# schematic.net
KiCad netlist of a schematic drawn in Altium Designer
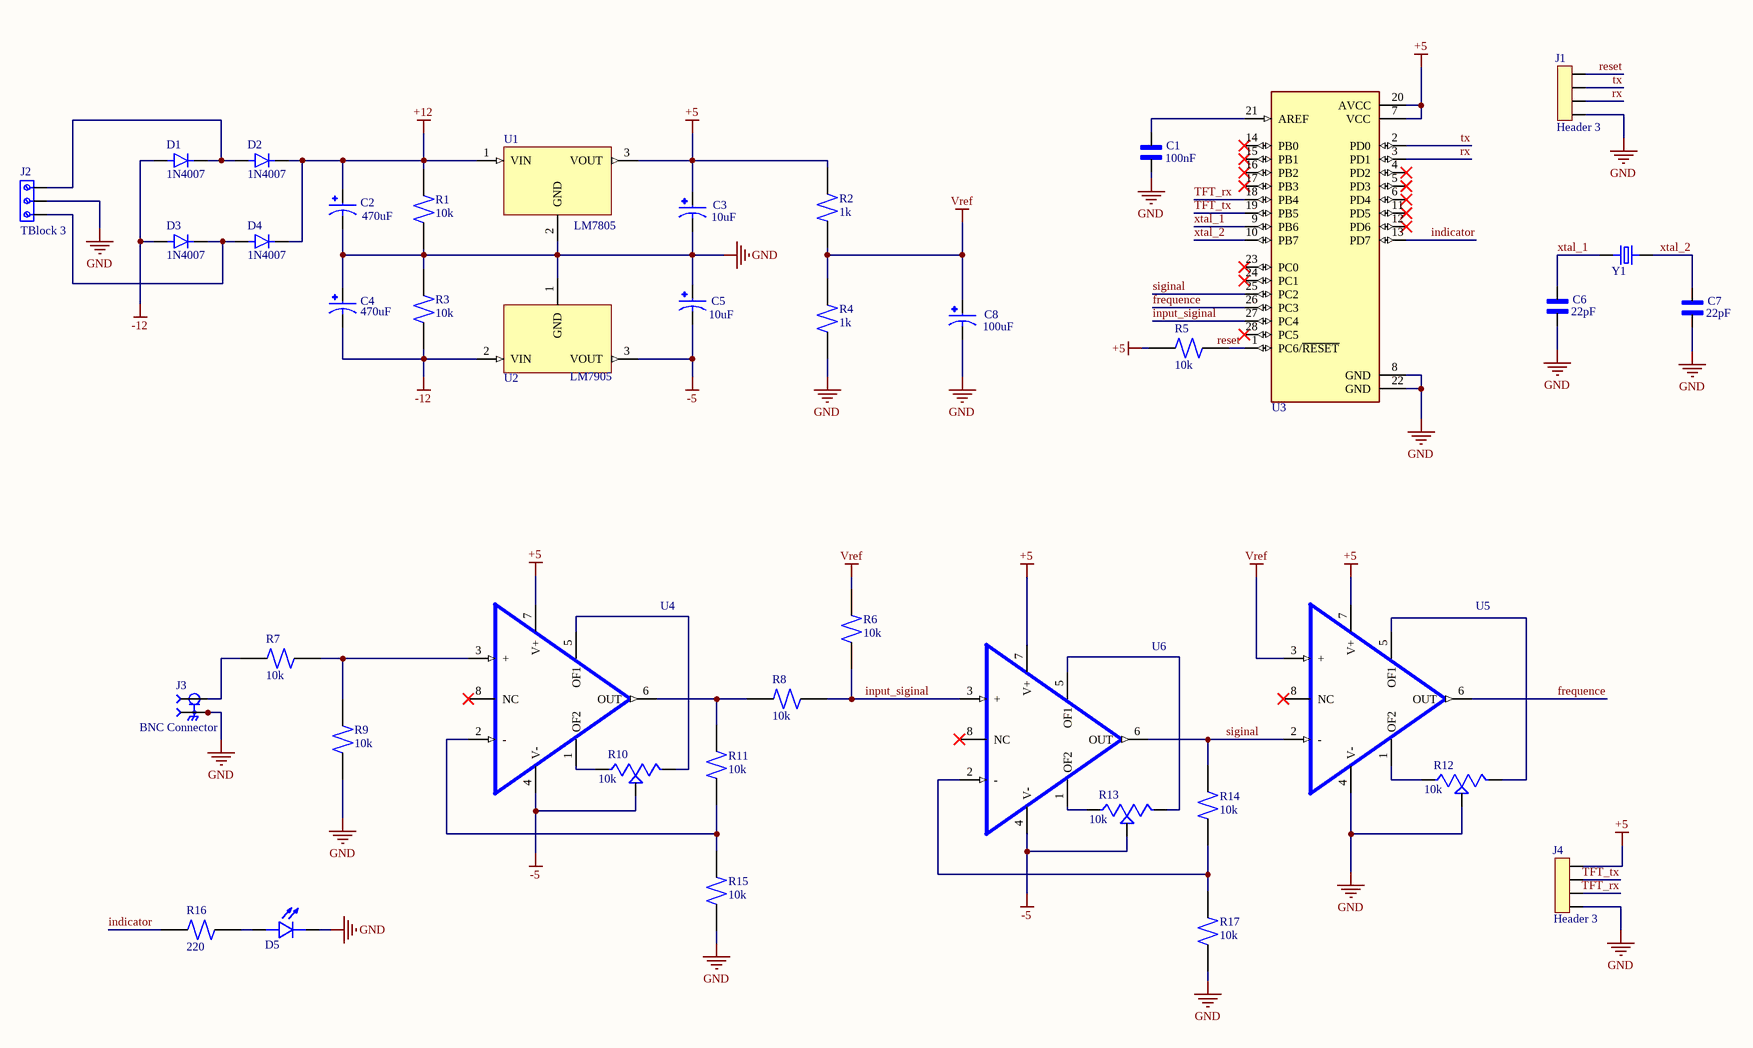
[diagram p0: schematic.SchDoc]

(export (version "E")
  (design (tool "Eeschema 10.0.6"))
  (components
    (comp (ref "C1")
      (value "100nF")
      (footprint "CAPRB500W50L450T300H550")
      (description "2200 pF Â±10% 250V Ceramic Capacitor X7R Radial")
      (fields (field (name "DIGI-KEY_PART_NUMBER") "445-173386-1-ND") (field (name "MF") "TDK"))
      (libsource (lib "Installed library") (part "Ceramic capacitor"))
    )
    (comp (ref "C2")
      (value "470uF")
      (footprint "CAPPRD500W50D500H1100")
      (description "FS-A")
      (fields (field (name "MF") "{'manufacturer': u'Panasonic'}") (field (name "MP") "EEUFS0J221B"))
      (libsource (lib "Installed library") (part "Electrolytic capacitor"))
    )
    (comp (ref "C3")
      (value "10uF")
      (footprint "CAPPRD500W50D500H1100")
      (description "FS-A")
      (fields (field (name "MF") "{'manufacturer': u'Panasonic'}") (field (name "MP") "EEUFS0J221B"))
      (libsource (lib "Installed library") (part "Electrolytic capacitor"))
    )
    (comp (ref "C4")
      (value "470uF")
      (footprint "CAPPRD500W50D500H1100")
      (description "FS-A")
      (fields (field (name "MF") "{'manufacturer': u'Panasonic'}") (field (name "MP") "EEUFS0J221B"))
      (libsource (lib "Installed library") (part "Electrolytic capacitor"))
    )
    (comp (ref "C5")
      (value "10uF")
      (footprint "CAPPRD500W50D500H1100")
      (description "FS-A")
      (fields (field (name "MF") "{'manufacturer': u'Panasonic'}") (field (name "MP") "EEUFS0J221B"))
      (libsource (lib "Installed library") (part "Electrolytic capacitor"))
    )
    (comp (ref "C6")
      (value "22pF")
      (footprint "CAPRB500W50L450T300H550")
      (description "2200 pF Â±10% 250V Ceramic Capacitor X7R Radial")
      (fields (field (name "DIGI-KEY_PART_NUMBER") "445-173386-1-ND") (field (name "MF") "TDK"))
      (libsource (lib "Installed library") (part "Ceramic capacitor"))
    )
    (comp (ref "C7")
      (value "22pF")
      (footprint "CAPRB500W50L450T300H550")
      (description "2200 pF Â±10% 250V Ceramic Capacitor X7R Radial")
      (fields (field (name "DIGI-KEY_PART_NUMBER") "445-173386-1-ND") (field (name "MF") "TDK"))
      (libsource (lib "Installed library") (part "Ceramic capacitor"))
    )
    (comp (ref "C8")
      (value "100uF")
      (footprint "CAPPRD500W50D500H1100")
      (description "FS-A")
      (fields (field (name "MF") "{'manufacturer': u'Panasonic'}") (field (name "MP") "EEUFS0J221B"))
      (libsource (lib "Installed library") (part "Electrolytic capacitor"))
    )
    (comp (ref "D1")
      (value "1N4007")
      (footprint "DIOAD1060W80L520D270")
      (description "Diode Switching 1KV 1A 2-Pin DO-41")
      (libsource (lib "Devices") (part "1N4007"))
    )
    (comp (ref "D2")
      (value "1N4007")
      (footprint "DIOAD1060W80L520D270")
      (description "Diode Switching 1KV 1A 2-Pin DO-41")
      (libsource (lib "Devices") (part "1N4007"))
    )
    (comp (ref "D3")
      (value "1N4007")
      (footprint "DIOAD1060W80L520D270")
      (description "Diode Switching 1KV 1A 2-Pin DO-41")
      (libsource (lib "Devices") (part "1N4007"))
    )
    (comp (ref "D4")
      (value "1N4007")
      (footprint "DIOAD1060W80L520D270")
      (description "Diode Switching 1KV 1A 2-Pin DO-41")
      (libsource (lib "Devices") (part "1N4007"))
    )
    (comp (ref "D5")
      (value "L08R5000Q1")
      (footprint "LEDRD254W57D500H1070")
      (description "LED, Orange, Through Hole, T-1 3/4 (5mm), 30 mA, 2.1 V, 635 nm")
      (fields (field (name "MF") "{'manufacturer': u'LED Technology'}"))
      (libsource (lib "Installed library") (part "LED"))
    )
    (comp (ref "J1")
      (value "Header 3")
      (footprint "SULLINS_PPTC041LFBN-RC")
      (description "4 Position Header Connector Through Hole")
      (fields (field (name "MP") "PPTC041LFBN-RC") (field (name "MF") "Sullins Connector"))
      (libsource (lib "Installed library") (part "Female header - 4Pins"))
    )
    (comp (ref "J2")
      (value "TBlock 3")
      (footprint "691214110003")
      (description "3 Position Wire to Board Terminal Block Horizontal with Board 0.138 (3.50mm) Through Hole")
      (fields (field (name "MF") "Wurth Elektronik") (field (name "MP") "691214110003"))
      (libsource (lib "Installed library") (part "Terminal blocks - 3Pins (Small)"))
    )
    (comp (ref "J3")
      (value "BNC Connector")
      (footprint "MOLEX_0731711640")
      (description "BNC Connector Jack, Female Socket 75Ohm Through Hole, Right Angle Solder")
      (fields (field (name "MF") "Molex") (field (name "MP") "0731711640"))
      (libsource (lib "Connectors") (part "BNC Connector"))
    )
    (comp (ref "J4")
      (value "Header 3")
      (footprint "SULLINS_PPTC041LFBN-RC")
      (description "4 Position Header Connector Through Hole")
      (fields (field (name "MP") "PPTC041LFBN-RC") (field (name "MF") "Sullins Connector"))
      (libsource (lib "Installed library") (part "Female header - 4Pins"))
    )
    (comp (ref "R1")
      (value "10k")
      (footprint "RESAD1100W55L680D260")
      (description "(MFR-25FBF52-10K) 10,2 kOhm bei 1% 0,25W, 1/4W Durchbohrlochwiderstand Axial Metal Film")
      (fields (field (name "DIGI-KEY_PART_NUMBER") "10.2KXBK-ND") (field (name "MF") "Yageo"))
      (libsource (lib "Installed library") (part "Resistor (0.25W)"))
    )
    (comp (ref "R2")
      (value "1k")
      (footprint "RESAD1100W55L680D260")
      (description "(MFR-25FBF52-10K) 10,2 kOhm bei 1% 0,25W, 1/4W Durchbohrlochwiderstand Axial Metal Film")
      (fields (field (name "DIGI-KEY_PART_NUMBER") "10.2KXBK-ND") (field (name "MF") "Yageo"))
      (libsource (lib "Installed library") (part "Resistor (0.25W)"))
    )
    (comp (ref "R3")
      (value "10k")
      (footprint "RESAD1100W55L680D260")
      (description "(MFR-25FBF52-10K) 10,2 kOhm bei 1% 0,25W, 1/4W Durchbohrlochwiderstand Axial Metal Film")
      (fields (field (name "DIGI-KEY_PART_NUMBER") "10.2KXBK-ND") (field (name "MF") "Yageo"))
      (libsource (lib "Installed library") (part "Resistor (0.25W)"))
    )
    (comp (ref "R4")
      (value "1k")
      (footprint "RESAD1100W55L680D260")
      (description "(MFR-25FBF52-10K) 10,2 kOhm bei 1% 0,25W, 1/4W Durchbohrlochwiderstand Axial Metal Film")
      (fields (field (name "DIGI-KEY_PART_NUMBER") "10.2KXBK-ND") (field (name "MF") "Yageo"))
      (libsource (lib "Installed library") (part "Resistor (0.25W)"))
    )
    (comp (ref "R5")
      (value "10k")
      (footprint "RESAD1100W55L680D260")
      (description "(MFR-25FBF52-10K) 10,2 kOhm bei 1% 0,25W, 1/4W Durchbohrlochwiderstand Axial Metal Film")
      (fields (field (name "DIGI-KEY_PART_NUMBER") "10.2KXBK-ND") (field (name "MF") "Yageo"))
      (libsource (lib "Installed library") (part "Resistor (0.25W)"))
    )
    (comp (ref "R6")
      (value "10k")
      (footprint "RESAD1100W55L680D260")
      (description "(MFR-25FBF52-10K) 10,2 kOhm bei 1% 0,25W, 1/4W Durchbohrlochwiderstand Axial Metal Film")
      (fields (field (name "DIGI-KEY_PART_NUMBER") "10.2KXBK-ND") (field (name "MF") "Yageo"))
      (libsource (lib "Installed library") (part "Resistor (0.25W)"))
    )
    (comp (ref "R7")
      (value "10k")
      (footprint "RESAD1100W55L680D260")
      (description "(MFR-25FBF52-10K) 10,2 kOhm bei 1% 0,25W, 1/4W Durchbohrlochwiderstand Axial Metal Film")
      (fields (field (name "DIGI-KEY_PART_NUMBER") "10.2KXBK-ND") (field (name "MF") "Yageo"))
      (libsource (lib "Installed library") (part "Resistor (0.25W)"))
    )
    (comp (ref "R8")
      (value "10k")
      (footprint "RESAD1100W55L680D260")
      (description "(MFR-25FBF52-10K) 10,2 kOhm bei 1% 0,25W, 1/4W Durchbohrlochwiderstand Axial Metal Film")
      (fields (field (name "DIGI-KEY_PART_NUMBER") "10.2KXBK-ND") (field (name "MF") "Yageo"))
      (libsource (lib "Installed library") (part "Resistor (0.25W)"))
    )
    (comp (ref "R9")
      (value "10k")
      (footprint "RESAD1100W55L680D260")
      (description "(MFR-25FBF52-10K) 10,2 kOhm bei 1% 0,25W, 1/4W Durchbohrlochwiderstand Axial Metal Film")
      (fields (field (name "DIGI-KEY_PART_NUMBER") "10.2KXBK-ND") (field (name "MF") "Yageo"))
      (libsource (lib "Installed library") (part "Resistor (0.25W)"))
    )
    (comp (ref "R10")
      (value "10k")
      (footprint "TRIM_3306F-1-105")
      (fields (field (name "MF") "Bourns") (field (name "MP") "3306F-1-105"))
      (libsource (lib "Installed library") (part "Potentiometer1"))
    )
    (comp (ref "R11")
      (value "10k")
      (footprint "RESAD1100W55L680D260")
      (description "(MFR-25FBF52-10K) 10,2 kOhm bei 1% 0,25W, 1/4W Durchbohrlochwiderstand Axial Metal Film")
      (fields (field (name "DIGI-KEY_PART_NUMBER") "10.2KXBK-ND") (field (name "MF") "Yageo"))
      (libsource (lib "Installed library") (part "Resistor (0.25W)"))
    )
    (comp (ref "R12")
      (value "10k")
      (footprint "TRIM_3306F-1-105")
      (fields (field (name "MF") "Bourns") (field (name "MP") "3306F-1-105"))
      (libsource (lib "Installed library") (part "Potentiometer1"))
    )
    (comp (ref "R13")
      (value "10k")
      (footprint "TRIM_3306F-1-105")
      (fields (field (name "MF") "Bourns") (field (name "MP") "3306F-1-105"))
      (libsource (lib "Installed library") (part "Potentiometer1"))
    )
    (comp (ref "R14")
      (value "10k")
      (footprint "RESAD1100W55L680D260")
      (description "(MFR-25FBF52-10K) 10,2 kOhm bei 1% 0,25W, 1/4W Durchbohrlochwiderstand Axial Metal Film")
      (fields (field (name "DIGI-KEY_PART_NUMBER") "10.2KXBK-ND") (field (name "MF") "Yageo"))
      (libsource (lib "Installed library") (part "Resistor (0.25W)"))
    )
    (comp (ref "R15")
      (value "10k")
      (footprint "RESAD1100W55L680D260")
      (description "(MFR-25FBF52-10K) 10,2 kOhm bei 1% 0,25W, 1/4W Durchbohrlochwiderstand Axial Metal Film")
      (fields (field (name "DIGI-KEY_PART_NUMBER") "10.2KXBK-ND") (field (name "MF") "Yageo"))
      (libsource (lib "Installed library") (part "Resistor (0.25W)"))
    )
    (comp (ref "R16")
      (value "220")
      (footprint "RESAD1100W55L680D260")
      (description "(MFR-25FBF52-10K) 10,2 kOhm bei 1% 0,25W, 1/4W Durchbohrlochwiderstand Axial Metal Film")
      (fields (field (name "DIGI-KEY_PART_NUMBER") "10.2KXBK-ND") (field (name "MF") "Yageo"))
      (libsource (lib "Installed library") (part "Resistor (0.25W)"))
    )
    (comp (ref "R17")
      (value "10k")
      (footprint "RESAD1100W55L680D260")
      (description "(MFR-25FBF52-10K) 10,2 kOhm bei 1% 0,25W, 1/4W Durchbohrlochwiderstand Axial Metal Film")
      (fields (field (name "DIGI-KEY_PART_NUMBER") "10.2KXBK-ND") (field (name "MF") "Yageo"))
      (libsource (lib "Installed library") (part "Resistor (0.25W)"))
    )
    (comp (ref "U1")
      (value "LM7805")
      (footprint "TO255P1020X450X1968-3")
      (fields (field (name "MP") "LM7805CT/NOPB"))
      (libsource (lib "Voltage regulator") (part "LM78__"))
    )
    (comp (ref "U2")
      (value "LM7905")
      (footprint "TO255P1020X450X1968-3")
      (libsource (lib "Voltage regulator") (part "LM79__"))
    )
    (comp (ref "U3")
      (value "ATMEGA328P-PU")
      (footprint "DIP794W46P254L2967H457Q28B")
      (description "ATmega Series 20 MHz 32 KB Flash 2 KB SRAM 8-Bit Microcontroller - DIP-28")
      (libsource (lib "Installed library") (part "ATMEGA328P-PU"))
    )
    (comp (ref "U4")
      (value "OP-Amp")
      (footprint "DIP254P762X508-8")
      (description "General Purpose Amplifier 1 Circuit - 8-DIP")
      (fields (field (name "MP") "LM741CN") (field (name "MF") "ON Semiconductor"))
      (libsource (lib "Installed library") (part "LM741CN"))
    )
    (comp (ref "U5")
      (value "OP-Amp")
      (footprint "DIP254P762X508-8")
      (description "General Purpose Amplifier 1 Circuit - 8-DIP")
      (fields (field (name "MP") "LM741CN") (field (name "MF") "ON Semiconductor"))
      (libsource (lib "Installed library") (part "LM741CN"))
    )
    (comp (ref "U6")
      (value "OP-Amp")
      (footprint "DIP254P762X508-8")
      (description "General Purpose Amplifier 1 Circuit - 8-DIP")
      (fields (field (name "MP") "LM741CN") (field (name "MF") "ON Semiconductor"))
      (libsource (lib "Installed library") (part "LM741CN"))
    )
    (comp (ref "Y1")
      (value "ECS-160-S-4")
      (footprint "XTAL_ECS-160-20-4X")
      (description "CRYSTAL T/H")
      (fields (field (name "MF") "{'manufacturer': u'ECS Inc.'}"))
      (libsource (lib "Installed library") (part "Crystal oscilator"))
    )
  )
  (nets
    (net (code "1") (name "+5") (class "Default")
      (node (ref "C3") (pin "P") (pinfunction "P_P") (pintype "passive"))
      (node (ref "J4") (pin "1") (pinfunction "1_1") (pintype "passive"))
      (node (ref "R2") (pin "1") (pinfunction "1_1") (pintype "passive"))
      (node (ref "R5") (pin "1") (pinfunction "1_1") (pintype "passive"))
      (node (ref "U1") (pin "3") (pinfunction "VOUT_3") (pintype "output"))
      (node (ref "U3") (pin "20") (pinfunction "AVCC_20") (pintype "power_in"))
      (node (ref "U3") (pin "7") (pinfunction "VCC_7") (pintype "power_in"))
      (node (ref "U4") (pin "7") (pinfunction "V+_7") (pintype "power_in"))
      (node (ref "U5") (pin "7") (pinfunction "V+_7") (pintype "power_in"))
      (node (ref "U6") (pin "7") (pinfunction "V+_7") (pintype "power_in"))
    )
    (net (code "2") (name "+12") (class "Default")
      (node (ref "C2") (pin "P") (pinfunction "P_P") (pintype "passive"))
      (node (ref "D2") (pin "C") (pinfunction "C_C") (pintype "passive"))
      (node (ref "D4") (pin "C") (pinfunction "C_C") (pintype "passive"))
      (node (ref "R1") (pin "1") (pinfunction "1_1") (pintype "passive"))
      (node (ref "U1") (pin "1") (pinfunction "VIN_1") (pintype "input"))
    )
    (net (code "3") (name "-5") (class "Default")
      (node (ref "C5") (pin "N") (pinfunction "N_N") (pintype "passive"))
      (node (ref "R10") (pin "2") (pinfunction "WIPER_2") (pintype "passive"))
      (node (ref "R13") (pin "2") (pinfunction "WIPER_2") (pintype "passive"))
      (node (ref "U2") (pin "3") (pinfunction "VOUT_3") (pintype "output"))
      (node (ref "U4") (pin "4") (pinfunction "V-_4") (pintype "power_in"))
      (node (ref "U6") (pin "4") (pinfunction "V-_4") (pintype "power_in"))
    )
    (net (code "4") (name "-12") (class "Default")
      (node (ref "C4") (pin "N") (pinfunction "N_N") (pintype "passive"))
      (node (ref "D1") (pin "A") (pinfunction "A_A") (pintype "passive"))
      (node (ref "D3") (pin "A") (pinfunction "A_A") (pintype "passive"))
      (node (ref "R3") (pin "2") (pinfunction "2_2") (pintype "passive"))
      (node (ref "U2") (pin "2") (pinfunction "VIN_2") (pintype "input"))
    )
    (net (code "5") (name "/TFT_rx") (class "Default")
      (node (ref "J4") (pin "3") (pinfunction "3_3") (pintype "passive"))
      (node (ref "U3") (pin "18") (pinfunction "PB4_18") (pintype "bidirectional"))
    )
    (net (code "6") (name "/TFT_tx") (class "Default")
      (node (ref "J4") (pin "2") (pinfunction "2_2") (pintype "passive"))
      (node (ref "U3") (pin "19") (pinfunction "PB5_19") (pintype "bidirectional"))
    )
    (net (code "7") (name "/frequence") (class "Default")
      (node (ref "U3") (pin "26") (pinfunction "PC3_26") (pintype "bidirectional"))
      (node (ref "U5") (pin "6") (pinfunction "OUT_6") (pintype "output"))
    )
    (net (code "8") (name "/indicator") (class "Default")
      (node (ref "R16") (pin "1") (pinfunction "1_1") (pintype "passive"))
      (node (ref "U3") (pin "13") (pinfunction "PD7_13") (pintype "bidirectional"))
    )
    (net (code "9") (name "/input_siginal") (class "Default")
      (node (ref "R6") (pin "1") (pinfunction "1_1") (pintype "passive"))
      (node (ref "R8") (pin "1") (pinfunction "1_1") (pintype "passive"))
      (node (ref "U3") (pin "27") (pinfunction "PC4_27") (pintype "bidirectional"))
      (node (ref "U6") (pin "3") (pinfunction "+_3") (pintype "input"))
    )
    (net (code "10") (name "/reset") (class "Default")
      (node (ref "J1") (pin "1") (pinfunction "1_1") (pintype "passive"))
      (node (ref "R5") (pin "2") (pinfunction "2_2") (pintype "passive"))
      (node (ref "U3") (pin "1") (pinfunction "PC6/~{RESET}_1") (pintype "bidirectional"))
    )
    (net (code "11") (name "/rx") (class "Default")
      (node (ref "J1") (pin "3") (pinfunction "3_3") (pintype "passive"))
      (node (ref "U3") (pin "3") (pinfunction "PD1_3") (pintype "bidirectional"))
    )
    (net (code "12") (name "/siginal") (class "Default")
      (node (ref "R14") (pin "2") (pinfunction "2_2") (pintype "passive"))
      (node (ref "U3") (pin "25") (pinfunction "PC2_25") (pintype "bidirectional"))
      (node (ref "U5") (pin "2") (pinfunction "-_2") (pintype "input"))
      (node (ref "U6") (pin "6") (pinfunction "OUT_6") (pintype "output"))
    )
    (net (code "13") (name "/tx") (class "Default")
      (node (ref "J1") (pin "2") (pinfunction "2_2") (pintype "passive"))
      (node (ref "U3") (pin "2") (pinfunction "PD0_2") (pintype "bidirectional"))
    )
    (net (code "14") (name "/xtal_1") (class "Default")
      (node (ref "C6") (pin "1") (pinfunction "1_1") (pintype "passive"))
      (node (ref "U3") (pin "9") (pinfunction "PB6_9") (pintype "bidirectional"))
      (node (ref "Y1") (pin "1") (pinfunction "1_1") (pintype "passive"))
    )
    (net (code "15") (name "/xtal_2") (class "Default")
      (node (ref "C7") (pin "1") (pinfunction "1_1") (pintype "passive"))
      (node (ref "U3") (pin "10") (pinfunction "PB7_10") (pintype "bidirectional"))
      (node (ref "Y1") (pin "2") (pinfunction "2_2") (pintype "passive"))
    )
    (net (code "16") (name "GND") (class "Default")
      (node (ref "C1") (pin "2") (pinfunction "2_2") (pintype "passive"))
      (node (ref "C2") (pin "N") (pinfunction "N_N") (pintype "passive"))
      (node (ref "C3") (pin "N") (pinfunction "N_N") (pintype "passive"))
      (node (ref "C4") (pin "P") (pinfunction "P_P") (pintype "passive"))
      (node (ref "C5") (pin "P") (pinfunction "P_P") (pintype "passive"))
      (node (ref "C6") (pin "2") (pinfunction "2_2") (pintype "passive"))
      (node (ref "C7") (pin "2") (pinfunction "2_2") (pintype "passive"))
      (node (ref "C8") (pin "N") (pinfunction "N_N") (pintype "passive"))
      (node (ref "D5") (pin "C") (pinfunction "C_C") (pintype "passive"))
      (node (ref "J1") (pin "4") (pinfunction "4_4") (pintype "passive"))
      (node (ref "J2") (pin "2") (pinfunction "2_2") (pintype "passive"))
      (node (ref "J3") (pin "2") (pinfunction "2_2") (pintype "passive"))
      (node (ref "J3") (pin "3") (pinfunction "2_3") (pintype "passive"))
      (node (ref "J3") (pin "4") (pinfunction "2_4") (pintype "passive"))
      (node (ref "J3") (pin "5") (pinfunction "2_5") (pintype "passive"))
      (node (ref "J4") (pin "4") (pinfunction "4_4") (pintype "passive"))
      (node (ref "R1") (pin "2") (pinfunction "2_2") (pintype "passive"))
      (node (ref "R12") (pin "2") (pinfunction "WIPER_2") (pintype "passive"))
      (node (ref "R15") (pin "1") (pinfunction "1_1") (pintype "passive"))
      (node (ref "R17") (pin "1") (pinfunction "1_1") (pintype "passive"))
      (node (ref "R3") (pin "1") (pinfunction "1_1") (pintype "passive"))
      (node (ref "R4") (pin "2") (pinfunction "2_2") (pintype "passive"))
      (node (ref "R9") (pin "2") (pinfunction "2_2") (pintype "passive"))
      (node (ref "U1") (pin "2") (pinfunction "GND_2") (pintype "passive"))
      (node (ref "U2") (pin "1") (pinfunction "GND_1") (pintype "passive"))
      (node (ref "U3") (pin "22") (pinfunction "GND_22") (pintype "power_in"))
      (node (ref "U3") (pin "8") (pinfunction "GND_8") (pintype "power_in"))
      (node (ref "U5") (pin "4") (pinfunction "V-_4") (pintype "power_in"))
    )
    (net (code "17") (name "Net-(D1-PadC)") (class "Default")
      (node (ref "D1") (pin "C") (pinfunction "C_C") (pintype "passive"))
      (node (ref "D2") (pin "A") (pinfunction "A_A") (pintype "passive"))
      (node (ref "J2") (pin "3") (pinfunction "3_3") (pintype "passive"))
    )
    (net (code "18") (name "Net-(D3-PadC)") (class "Default")
      (node (ref "D3") (pin "C") (pinfunction "C_C") (pintype "passive"))
      (node (ref "D4") (pin "A") (pinfunction "A_A") (pintype "passive"))
      (node (ref "J2") (pin "1") (pinfunction "1_1") (pintype "passive"))
    )
    (net (code "19") (name "Net-(D5-PadA)") (class "Default")
      (node (ref "D5") (pin "A") (pinfunction "A_A") (pintype "passive"))
      (node (ref "R16") (pin "2") (pinfunction "2_2") (pintype "passive"))
    )
    (net (code "20") (name "Net-(J3-Pad1)") (class "Default")
      (node (ref "J3") (pin "1") (pinfunction "1_1") (pintype "passive"))
      (node (ref "R7") (pin "2") (pinfunction "2_2") (pintype "passive"))
    )
    (net (code "21") (name "Net-(R10-CCW)") (class "Default")
      (node (ref "R10") (pin "1") (pinfunction "CCW_1") (pintype "passive"))
      (node (ref "U4") (pin "1") (pinfunction "OF2_1") (pintype "passive"))
    )
    (net (code "22") (name "Net-(R10-CW)") (class "Default")
      (node (ref "R10") (pin "3") (pinfunction "CW_3") (pintype "passive"))
      (node (ref "U4") (pin "5") (pinfunction "OF1_5") (pintype "passive"))
    )
    (net (code "23") (name "Net-(R12-CCW)") (class "Default")
      (node (ref "R12") (pin "1") (pinfunction "CCW_1") (pintype "passive"))
      (node (ref "U5") (pin "1") (pinfunction "OF2_1") (pintype "passive"))
    )
    (net (code "24") (name "Net-(R12-CW)") (class "Default")
      (node (ref "R12") (pin "3") (pinfunction "CW_3") (pintype "passive"))
      (node (ref "U5") (pin "5") (pinfunction "OF1_5") (pintype "passive"))
    )
    (net (code "25") (name "Net-(R13-CCW)") (class "Default")
      (node (ref "R13") (pin "1") (pinfunction "CCW_1") (pintype "passive"))
      (node (ref "U6") (pin "1") (pinfunction "OF2_1") (pintype "passive"))
    )
    (net (code "26") (name "Net-(R13-CW)") (class "Default")
      (node (ref "R13") (pin "3") (pinfunction "CW_3") (pintype "passive"))
      (node (ref "U6") (pin "5") (pinfunction "OF1_5") (pintype "passive"))
    )
    (net (code "27") (name "Net-(U3-AREF)") (class "Default")
      (node (ref "C1") (pin "1") (pinfunction "1_1") (pintype "passive"))
      (node (ref "U3") (pin "21") (pinfunction "AREF_21") (pintype "input"))
    )
    (net (code "28") (name "Net-(U4-+)") (class "Default")
      (node (ref "R7") (pin "1") (pinfunction "1_1") (pintype "passive"))
      (node (ref "R9") (pin "1") (pinfunction "1_1") (pintype "passive"))
      (node (ref "U4") (pin "3") (pinfunction "+_3") (pintype "input"))
    )
    (net (code "29") (name "Net-(U4--)") (class "Default")
      (node (ref "R11") (pin "1") (pinfunction "1_1") (pintype "passive"))
      (node (ref "R15") (pin "2") (pinfunction "2_2") (pintype "passive"))
      (node (ref "U4") (pin "2") (pinfunction "-_2") (pintype "input"))
    )
    (net (code "30") (name "Net-(U4-OUT)") (class "Default")
      (node (ref "R11") (pin "2") (pinfunction "2_2") (pintype "passive"))
      (node (ref "R8") (pin "2") (pinfunction "2_2") (pintype "passive"))
      (node (ref "U4") (pin "6") (pinfunction "OUT_6") (pintype "output"))
    )
    (net (code "31") (name "Net-(U6--)") (class "Default")
      (node (ref "R14") (pin "1") (pinfunction "1_1") (pintype "passive"))
      (node (ref "R17") (pin "2") (pinfunction "2_2") (pintype "passive"))
      (node (ref "U6") (pin "2") (pinfunction "-_2") (pintype "input"))
    )
    (net (code "32") (name "Vref") (class "Default")
      (node (ref "C8") (pin "P") (pinfunction "P_P") (pintype "passive"))
      (node (ref "R2") (pin "2") (pinfunction "2_2") (pintype "passive"))
      (node (ref "R4") (pin "1") (pinfunction "1_1") (pintype "passive"))
      (node (ref "R6") (pin "2") (pinfunction "2_2") (pintype "passive"))
      (node (ref "U5") (pin "3") (pinfunction "+_3") (pintype "input"))
    )
    (net (code "33") (name "unconnected-(U3-PB0-Pad14)") (class "Default")
      (node (ref "U3") (pin "14") (pinfunction "PB0_14") (pintype "bidirectional+no_connect"))
    )
    (net (code "34") (name "unconnected-(U3-PB1-Pad15)") (class "Default")
      (node (ref "U3") (pin "15") (pinfunction "PB1_15") (pintype "bidirectional+no_connect"))
    )
    (net (code "35") (name "unconnected-(U3-PB2-Pad16)") (class "Default")
      (node (ref "U3") (pin "16") (pinfunction "PB2_16") (pintype "bidirectional+no_connect"))
    )
    (net (code "36") (name "unconnected-(U3-PB3-Pad17)") (class "Default")
      (node (ref "U3") (pin "17") (pinfunction "PB3_17") (pintype "bidirectional+no_connect"))
    )
    (net (code "37") (name "unconnected-(U3-PC0-Pad23)") (class "Default")
      (node (ref "U3") (pin "23") (pinfunction "PC0_23") (pintype "bidirectional+no_connect"))
    )
    (net (code "38") (name "unconnected-(U3-PC1-Pad24)") (class "Default")
      (node (ref "U3") (pin "24") (pinfunction "PC1_24") (pintype "bidirectional+no_connect"))
    )
    (net (code "39") (name "unconnected-(U3-PC5-Pad28)") (class "Default")
      (node (ref "U3") (pin "28") (pinfunction "PC5_28") (pintype "bidirectional+no_connect"))
    )
    (net (code "40") (name "unconnected-(U3-PD2-Pad4)") (class "Default")
      (node (ref "U3") (pin "4") (pinfunction "PD2_4") (pintype "bidirectional+no_connect"))
    )
    (net (code "41") (name "unconnected-(U3-PD3-Pad5)") (class "Default")
      (node (ref "U3") (pin "5") (pinfunction "PD3_5") (pintype "bidirectional+no_connect"))
    )
    (net (code "42") (name "unconnected-(U3-PD4-Pad6)") (class "Default")
      (node (ref "U3") (pin "6") (pinfunction "PD4_6") (pintype "bidirectional+no_connect"))
    )
    (net (code "43") (name "unconnected-(U3-PD5-Pad11)") (class "Default")
      (node (ref "U3") (pin "11") (pinfunction "PD5_11") (pintype "bidirectional+no_connect"))
    )
    (net (code "44") (name "unconnected-(U3-PD6-Pad12)") (class "Default")
      (node (ref "U3") (pin "12") (pinfunction "PD6_12") (pintype "bidirectional+no_connect"))
    )
    (net (code "45") (name "unconnected-(U4-NC-Pad8)") (class "Default")
      (node (ref "U4") (pin "8") (pinfunction "NC_8") (pintype "passive+no_connect"))
    )
    (net (code "46") (name "unconnected-(U5-NC-Pad8)") (class "Default")
      (node (ref "U5") (pin "8") (pinfunction "NC_8") (pintype "passive+no_connect"))
    )
    (net (code "47") (name "unconnected-(U6-NC-Pad8)") (class "Default")
      (node (ref "U6") (pin "8") (pinfunction "NC_8") (pintype "passive+no_connect"))
    )
  )
)
